# noroshi_LoRa.net
KiCad netlist of a schematic drawn in EAGLE
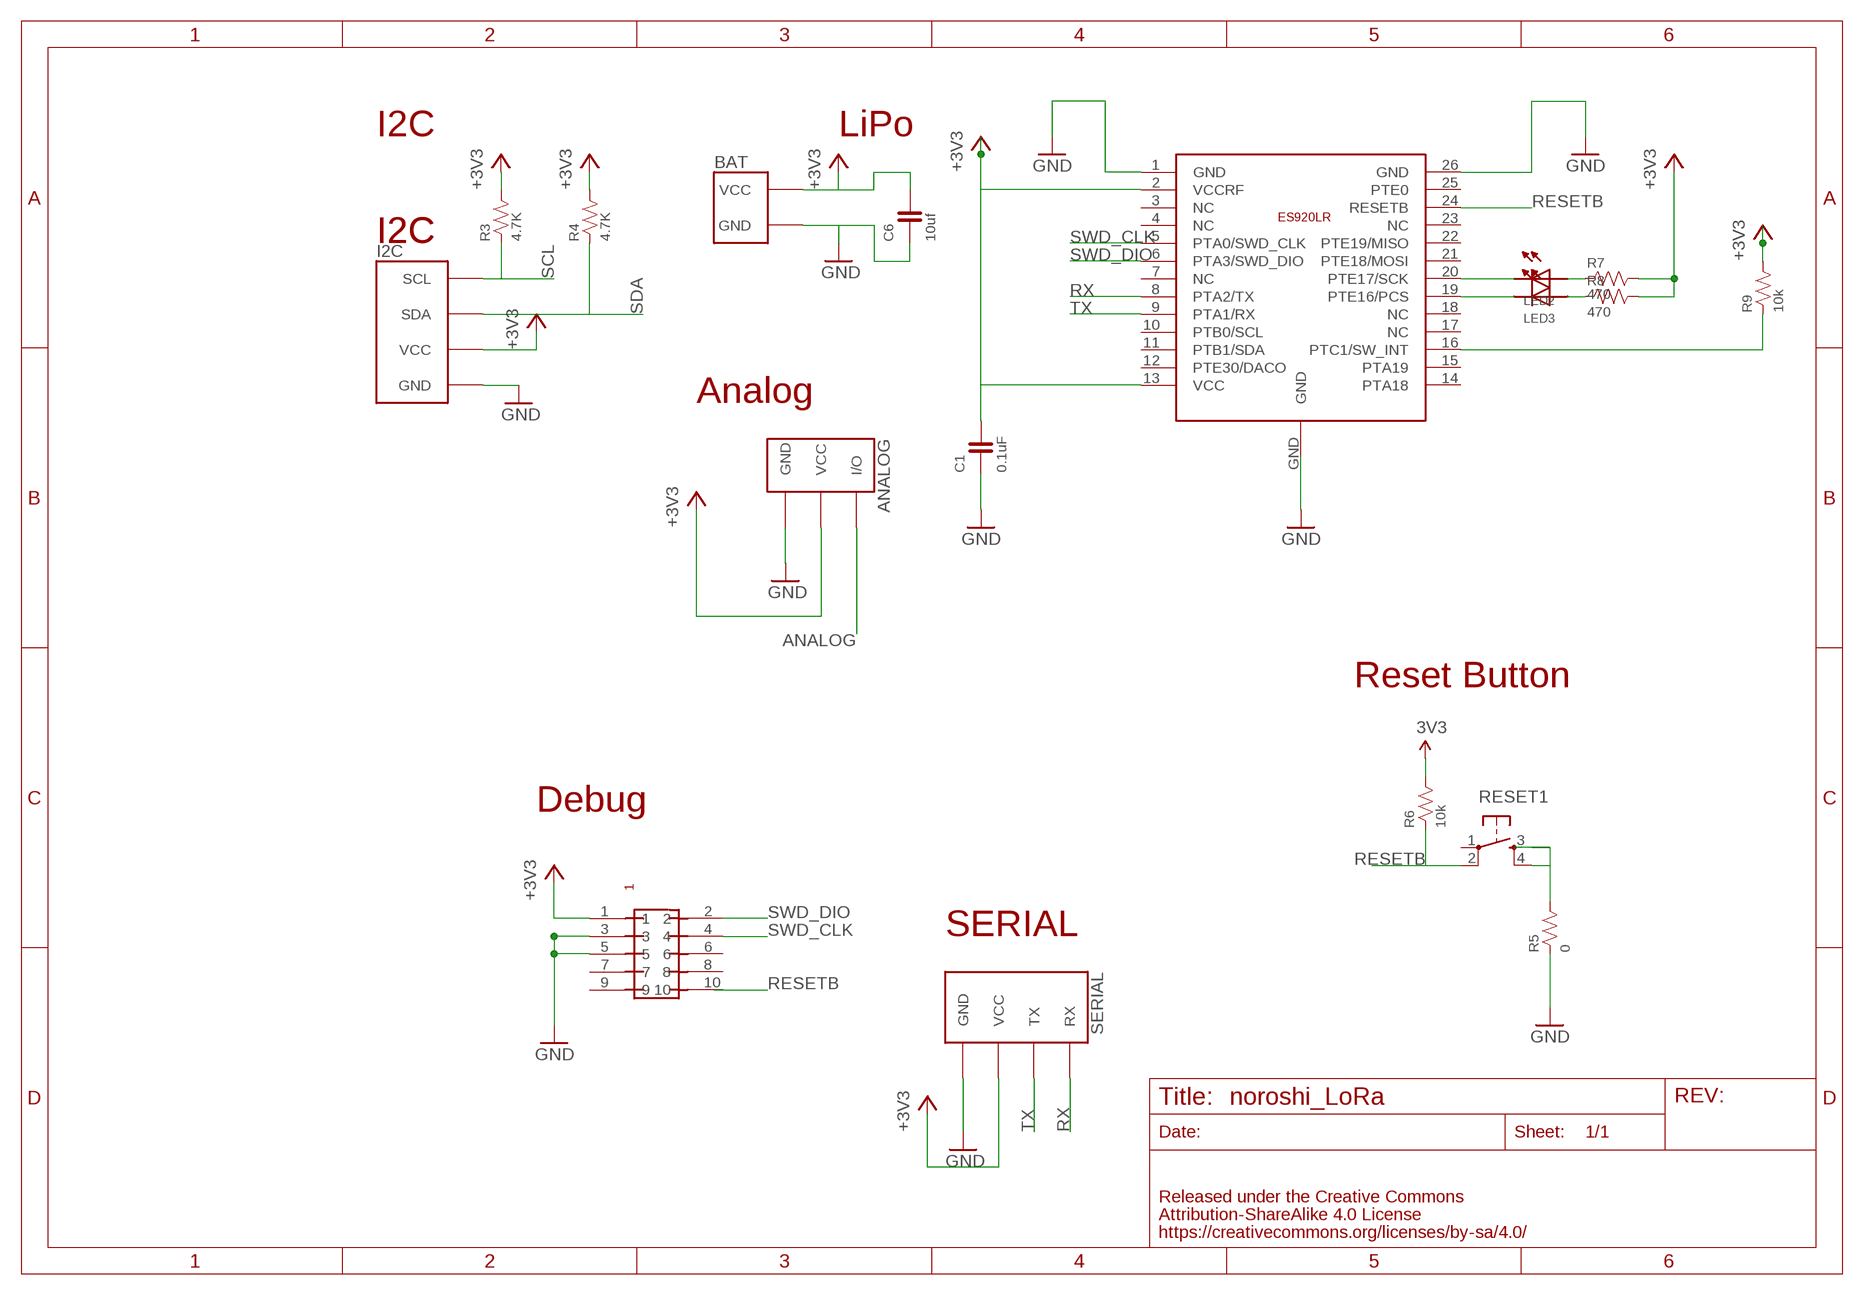
[diagram p0: schematic, sheet 1]

(export (version "E")
  (design (tool "Eeschema 10.0.6"))
  (components
    (comp (ref "ANALOG")
      (value "FABO_BRICK_3PIN-S03B-PASK-2_LONG")
      (footprint "eagle-import:FABO_BRICK_3PIN_S03B-PASK-2_LONG")
      (libsource (lib "eagle-import") (part "FABO_BRICK_3PIN-S03B-PASK-2_LONG"))
    )
    (comp (ref "BAT")
      (value "FABO_BRICK_2PIN_SIDE")
      (footprint "eagle-import:FABO_BRICK_2PIN_S02B−PASK-2_SILK")
      (libsource (lib "eagle-import") (part "FABO_BRICK_2PIN_SIDE"))
    )
    (comp (ref "C1")
      (value "0.1uF")
      (footprint "eagle-import:0603-NARROW")
      (libsource (lib "eagle-import") (part "CAPACITOR-0603_NARROW"))
    )
    (comp (ref "C6")
      (value "10uf")
      (footprint "eagle-import:0603")
      (libsource (lib "eagle-import") (part "CAPACITOR-0603"))
    )
    (comp (ref "I2C")
      (value "FABO_BRICK_I2C-S04B-PASK-2_LONG")
      (footprint "eagle-import:FABO_BRICK_I2C_S04B-PASK-2_LONG")
      (libsource (lib "eagle-import") (part "FABO_BRICK_I2C-S04B-PASK-2_LONG"))
    )
    (comp (ref "LED2")
      (value "LED-0603")
      (footprint "eagle-import:0603")
      (libsource (lib "eagle-import") (part "LED-0603"))
    )
    (comp (ref "LED3")
      (value "LED-0603")
      (footprint "eagle-import:0603")
      (libsource (lib "eagle-import") (part "LED-0603"))
    )
    (comp (ref "R3")
      (value "4.7K")
      (footprint "eagle-import:0603")
      (libsource (lib "eagle-import") (part "RESISTOR-0603"))
    )
    (comp (ref "R4")
      (value "4.7K")
      (footprint "eagle-import:0603")
      (libsource (lib "eagle-import") (part "RESISTOR-0603"))
    )
    (comp (ref "R5")
      (value "0")
      (footprint "eagle-import:0603-NARROW")
      (libsource (lib "eagle-import") (part "RESISTOR-0603-NARROW"))
    )
    (comp (ref "R6")
      (value "10k")
      (footprint "eagle-import:0603-NARROW")
      (libsource (lib "eagle-import") (part "RESISTOR-0603-NARROW"))
    )
    (comp (ref "R7")
      (value "470")
      (footprint "eagle-import:0603-NARROW")
      (libsource (lib "eagle-import") (part "RESISTOR-0603-NARROW"))
    )
    (comp (ref "R8")
      (value "470")
      (footprint "eagle-import:0603-NARROW")
      (libsource (lib "eagle-import") (part "RESISTOR-0603-NARROW"))
    )
    (comp (ref "R9")
      (value "10k")
      (footprint "eagle-import:0603-NARROW")
      (libsource (lib "eagle-import") (part "RESISTOR-0603-NARROW"))
    )
    (comp (ref "RESET1")
      (value "TACT-SWITCH-SMD_KMR2")
      (footprint "eagle-import:KMR2")
      (libsource (lib "eagle-import") (part "TACT-SWITCH-SMD_KMR2"))
    )
    (comp (ref "SERIAL")
      (value "FABO_BRICK_SERIAL-S04B-PASK-2_LONG")
      (footprint "eagle-import:FABO_BRICK_SERIAL_S04B-PASK-2_LONG")
      (libsource (lib "eagle-import") (part "FABO_BRICK_SERIAL-S04B-PASK-2_LONG"))
    )
    (comp (ref "U$2")
      (value "ES920LR")
      (footprint "eagle-import:ES920LR")
      (libsource (lib "eagle-import") (part "ES920LR"))
    )
    (comp (ref "U$8")
      (value "PIN-HEADER-SMT(1.27MM)2X5")
      (footprint "eagle-import:PIN-HEADER-SMT(1.27MM)2X5")
      (libsource (lib "eagle-import") (part "PIN-HEADER-SMT(1.27MM)2X5"))
    )
  )
  (nets
    (net (code "1") (name "+3V3") (class "Default")
      (node (ref "ANALOG") (pin "VCC") (pinfunction "VCC_VCC") (pintype "bidirectional"))
      (node (ref "BAT") (pin "VCC") (pinfunction "VCC_VCC") (pintype "bidirectional"))
      (node (ref "C1") (pin "2") (pinfunction "2_2") (pintype "passive"))
      (node (ref "C6") (pin "2") (pinfunction "2_2") (pintype "passive"))
      (node (ref "I2C") (pin "VCC") (pinfunction "VCC_VCC") (pintype "bidirectional"))
      (node (ref "R3") (pin "2") (pinfunction "2_2") (pintype "bidirectional"))
      (node (ref "R4") (pin "2") (pinfunction "2_2") (pintype "bidirectional"))
      (node (ref "R7") (pin "2") (pinfunction "2_2") (pintype "bidirectional"))
      (node (ref "R8") (pin "2") (pinfunction "2_2") (pintype "bidirectional"))
      (node (ref "R9") (pin "2") (pinfunction "2_2") (pintype "bidirectional"))
      (node (ref "SERIAL") (pin "VCC") (pinfunction "VCC_VCC") (pintype "bidirectional"))
      (node (ref "U$2") (pin "13") (pinfunction "VCC_13") (pintype "bidirectional"))
      (node (ref "U$2") (pin "2") (pinfunction "VCCRF_2") (pintype "bidirectional"))
      (node (ref "U$8") (pin "1") (pinfunction "1_1") (pintype "bidirectional"))
    )
    (net (code "2") (name "/ANALOG") (class "Default")
      (node (ref "ANALOG") (pin "I/O") (pinfunction "I/O_I/O") (pintype "bidirectional"))
    )
    (net (code "3") (name "/RESETB") (class "Default")
      (node (ref "R6") (pin "1") (pinfunction "1_1") (pintype "bidirectional"))
      (node (ref "RESET1") (pin "2") (pinfunction "2_2") (pintype "passive"))
      (node (ref "U$2") (pin "24") (pinfunction "RESETB_24") (pintype "bidirectional"))
      (node (ref "U$8") (pin "10") (pinfunction "10_10") (pintype "bidirectional"))
    )
    (net (code "4") (name "/RX") (class "Default")
      (node (ref "SERIAL") (pin "RX") (pinfunction "RX_RX") (pintype "bidirectional"))
      (node (ref "U$2") (pin "8") (pinfunction "PTA2/TX_8") (pintype "bidirectional"))
    )
    (net (code "5") (name "/SCL") (class "Default")
      (node (ref "I2C") (pin "SCL") (pinfunction "SCL_SCL") (pintype "bidirectional"))
      (node (ref "R3") (pin "1") (pinfunction "1_1") (pintype "bidirectional"))
    )
    (net (code "6") (name "/SDA") (class "Default")
      (node (ref "I2C") (pin "SDA") (pinfunction "SDA_SDA") (pintype "bidirectional"))
      (node (ref "R4") (pin "1") (pinfunction "1_1") (pintype "bidirectional"))
    )
    (net (code "7") (name "/SWD_CLK") (class "Default")
      (node (ref "U$2") (pin "5") (pinfunction "PTA0/SWD_CLK_5") (pintype "bidirectional"))
      (node (ref "U$8") (pin "4") (pinfunction "4_4") (pintype "bidirectional"))
    )
    (net (code "8") (name "/SWD_DIO") (class "Default")
      (node (ref "U$2") (pin "6") (pinfunction "PTA3/SWD_DIO_6") (pintype "bidirectional"))
      (node (ref "U$8") (pin "2") (pinfunction "2_2") (pintype "bidirectional"))
    )
    (net (code "9") (name "/TX") (class "Default")
      (node (ref "SERIAL") (pin "TX") (pinfunction "TX_TX") (pintype "bidirectional"))
      (node (ref "U$2") (pin "9") (pinfunction "PTA1/RX_9") (pintype "bidirectional"))
    )
    (net (code "10") (name "3V3") (class "Default")
      (node (ref "R6") (pin "2") (pinfunction "2_2") (pintype "bidirectional"))
    )
    (net (code "11") (name "GND") (class "Default")
      (node (ref "ANALOG") (pin "GND") (pinfunction "GND_GND") (pintype "bidirectional"))
      (node (ref "BAT") (pin "GND") (pinfunction "GND_GND") (pintype "bidirectional"))
      (node (ref "C1") (pin "1") (pinfunction "1_1") (pintype "passive"))
      (node (ref "C6") (pin "1") (pinfunction "1_1") (pintype "passive"))
      (node (ref "I2C") (pin "GND") (pinfunction "GND_GND") (pintype "bidirectional"))
      (node (ref "R5") (pin "1") (pinfunction "1_1") (pintype "bidirectional"))
      (node (ref "SERIAL") (pin "GND") (pinfunction "GND_GND") (pintype "bidirectional"))
      (node (ref "U$2") (pin "1") (pinfunction "GND_1") (pintype "bidirectional"))
      (node (ref "U$2") (pin "26") (pinfunction "GND_26") (pintype "bidirectional"))
      (node (ref "U$2") (pin "GND") (pinfunction "GND_GND") (pintype "bidirectional"))
      (node (ref "U$8") (pin "3") (pinfunction "3_3") (pintype "bidirectional"))
      (node (ref "U$8") (pin "5") (pinfunction "5_5") (pintype "bidirectional"))
    )
    (net (code "12") (name "Net-(LED2-PadANODE)") (class "Default")
      (node (ref "LED2") (pin "ANODE") (pinfunction "ANODE_ANODE") (pintype "passive"))
      (node (ref "R7") (pin "1") (pinfunction "1_1") (pintype "bidirectional"))
    )
    (net (code "13") (name "Net-(LED3-PadANODE)") (class "Default")
      (node (ref "LED3") (pin "ANODE") (pinfunction "ANODE_ANODE") (pintype "passive"))
      (node (ref "R8") (pin "1") (pinfunction "1_1") (pintype "bidirectional"))
    )
    (net (code "14") (name "Net-(R5-Pad2)") (class "Default")
      (node (ref "R5") (pin "2") (pinfunction "2_2") (pintype "bidirectional"))
      (node (ref "RESET1") (pin "3") (pinfunction "3_3") (pintype "passive"))
      (node (ref "RESET1") (pin "4") (pinfunction "4_4") (pintype "passive"))
    )
    (net (code "15") (name "Net-(U$2-PTC1{slash}SW_INT)") (class "Default")
      (node (ref "R9") (pin "1") (pinfunction "1_1") (pintype "bidirectional"))
      (node (ref "U$2") (pin "16") (pinfunction "PTC1/SW_INT_16") (pintype "bidirectional"))
    )
    (net (code "16") (name "Net-(U$2-PTE16{slash}PCS)") (class "Default")
      (node (ref "LED3") (pin "CATHODE") (pinfunction "CATHODE_CATHODE") (pintype "passive"))
      (node (ref "U$2") (pin "19") (pinfunction "PTE16/PCS_19") (pintype "bidirectional"))
    )
    (net (code "17") (name "Net-(U$2-PTE17{slash}SCK)") (class "Default")
      (node (ref "LED2") (pin "CATHODE") (pinfunction "CATHODE_CATHODE") (pintype "passive"))
      (node (ref "U$2") (pin "20") (pinfunction "PTE17/SCK_20") (pintype "bidirectional"))
    )
    (net (code "18") (name "unconnected-(RESET1-Pad1)") (class "Default")
      (node (ref "RESET1") (pin "1") (pinfunction "1_1") (pintype "passive"))
    )
    (net (code "19") (name "unconnected-(U$2-NC-Pad3)") (class "Default")
      (node (ref "U$2") (pin "3") (pinfunction "NC_3") (pintype "bidirectional"))
    )
    (net (code "20") (name "unconnected-(U$2-NC-Pad4)") (class "Default")
      (node (ref "U$2") (pin "4") (pinfunction "NC_4") (pintype "bidirectional"))
    )
    (net (code "21") (name "unconnected-(U$2-NC-Pad7)") (class "Default")
      (node (ref "U$2") (pin "7") (pinfunction "NC_7") (pintype "bidirectional"))
    )
    (net (code "22") (name "unconnected-(U$2-NC-Pad17)") (class "Default")
      (node (ref "U$2") (pin "17") (pinfunction "NC_17") (pintype "bidirectional"))
    )
    (net (code "23") (name "unconnected-(U$2-NC-Pad18)") (class "Default")
      (node (ref "U$2") (pin "18") (pinfunction "NC_18") (pintype "bidirectional"))
    )
    (net (code "24") (name "unconnected-(U$2-NC-Pad23)") (class "Default")
      (node (ref "U$2") (pin "23") (pinfunction "NC_23") (pintype "bidirectional"))
    )
    (net (code "25") (name "unconnected-(U$2-PTA18-Pad14)") (class "Default")
      (node (ref "U$2") (pin "14") (pinfunction "PTA18_14") (pintype "bidirectional"))
    )
    (net (code "26") (name "unconnected-(U$2-PTA19-Pad15)") (class "Default")
      (node (ref "U$2") (pin "15") (pinfunction "PTA19_15") (pintype "bidirectional"))
    )
    (net (code "27") (name "unconnected-(U$2-PTB0{slash}SCL-Pad10)") (class "Default")
      (node (ref "U$2") (pin "10") (pinfunction "PTB0/SCL_10") (pintype "bidirectional"))
    )
    (net (code "28") (name "unconnected-(U$2-PTB1{slash}SDA-Pad11)") (class "Default")
      (node (ref "U$2") (pin "11") (pinfunction "PTB1/SDA_11") (pintype "bidirectional"))
    )
    (net (code "29") (name "unconnected-(U$2-PTE0-Pad25)") (class "Default")
      (node (ref "U$2") (pin "25") (pinfunction "PTE0_25") (pintype "bidirectional"))
    )
    (net (code "30") (name "unconnected-(U$2-PTE18{slash}MOSI-Pad21)") (class "Default")
      (node (ref "U$2") (pin "21") (pinfunction "PTE18/MOSI_21") (pintype "bidirectional"))
    )
    (net (code "31") (name "unconnected-(U$2-PTE19{slash}MISO-Pad22)") (class "Default")
      (node (ref "U$2") (pin "22") (pinfunction "PTE19/MISO_22") (pintype "bidirectional"))
    )
    (net (code "32") (name "unconnected-(U$2-PTE30{slash}DACO-Pad12)") (class "Default")
      (node (ref "U$2") (pin "12") (pinfunction "PTE30/DACO_12") (pintype "bidirectional"))
    )
    (net (code "33") (name "unconnected-(U$8-Pad6)") (class "Default")
      (node (ref "U$8") (pin "6") (pinfunction "6_6") (pintype "bidirectional"))
    )
    (net (code "34") (name "unconnected-(U$8-Pad7)") (class "Default")
      (node (ref "U$8") (pin "7") (pinfunction "7_7") (pintype "bidirectional"))
    )
    (net (code "35") (name "unconnected-(U$8-Pad8)") (class "Default")
      (node (ref "U$8") (pin "8") (pinfunction "8_8") (pintype "bidirectional"))
    )
    (net (code "36") (name "unconnected-(U$8-Pad9)") (class "Default")
      (node (ref "U$8") (pin "9") (pinfunction "9_9") (pintype "bidirectional"))
    )
  )
)
